# 4_Channel_ADC.net
KiCad netlist of a schematic drawn in Altium Designer
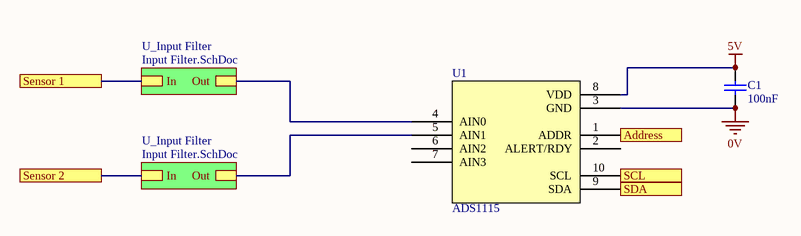
[diagram p0: 4 Channel ADC.SchDoc]

(export (version "E")
  (design (tool "Eeschema 10.0.6"))
  (components
    (comp (ref "C1")
      (value "100nF")
      (footprint "0805")
      (fields
        (field (name "PART NUMBER") "GCM21BR71E104KA37L")
        (field (name "TOLERANCE") "10%")
        (field (name "MANUFACTURER") "muRata")
      )
      (libsource (lib "ts_20-standard-library") (part "Capacitor"))
    )
    (comp (ref "U1")
      (value "ADS1115")
      (footprint "TI 10-VSSOP")
      (description "16 Bit Analog to Digital Converter 2, 4 Input 1 Sigma-Delta 10-VSSOP")
      (fields
        (field (name "MANUFACTURER") "Texas Instruments")
        (field (name "DIGIKEY PART NUMBER") "296-38849-1-ND")
      )
      (libsource (lib "ts_20-standard-library") (part "ADS1115"))
    )
  )
  (nets
    (net (code "1") (name "/Address") (class "Default")
      (node (ref "U1") (pin "1") (pinfunction "ADDR_1") (pintype "passive"))
    )
    (net (code "2") (name "/Out") (class "Default")
      (node (ref "U1") (pin "5") (pinfunction "AIN1_5") (pintype "passive"))
    )
    (net (code "3") (name "/Out_1") (class "Default")
      (node (ref "U1") (pin "4") (pinfunction "AIN0_4") (pintype "passive"))
    )
    (net (code "4") (name "/SCL") (class "Default")
      (node (ref "U1") (pin "10") (pinfunction "SCL_10") (pintype "passive"))
    )
    (net (code "5") (name "/SDA") (class "Default")
      (node (ref "U1") (pin "9") (pinfunction "SDA_9") (pintype "passive"))
    )
    (net (code "8") (name "0V") (class "Default")
      (node (ref "C1") (pin "1") (pinfunction "1_1") (pintype "passive"))
      (node (ref "U1") (pin "3") (pinfunction "GND_3") (pintype "passive"))
    )
    (net (code "9") (name "5V") (class "Default")
      (node (ref "C1") (pin "2") (pinfunction "2_2") (pintype "passive"))
      (node (ref "U1") (pin "8") (pinfunction "VDD_8") (pintype "passive"))
    )
    (net (code "10") (name "unconnected-(U1-AIN2-Pad6)") (class "Default")
      (node (ref "U1") (pin "6") (pinfunction "AIN2_6") (pintype "passive"))
    )
    (net (code "11") (name "unconnected-(U1-AIN3-Pad7)") (class "Default")
      (node (ref "U1") (pin "7") (pinfunction "AIN3_7") (pintype "passive"))
    )
    (net (code "12") (name "unconnected-(U1-ALERT{slash}RDY-Pad2)") (class "Default")
      (node (ref "U1") (pin "2") (pinfunction "ALERT/RDY_2") (pintype "passive"))
    )
  )
)
